# ESP32_with_USB_C.net
KiCad netlist of a schematic drawn in Altium Designer
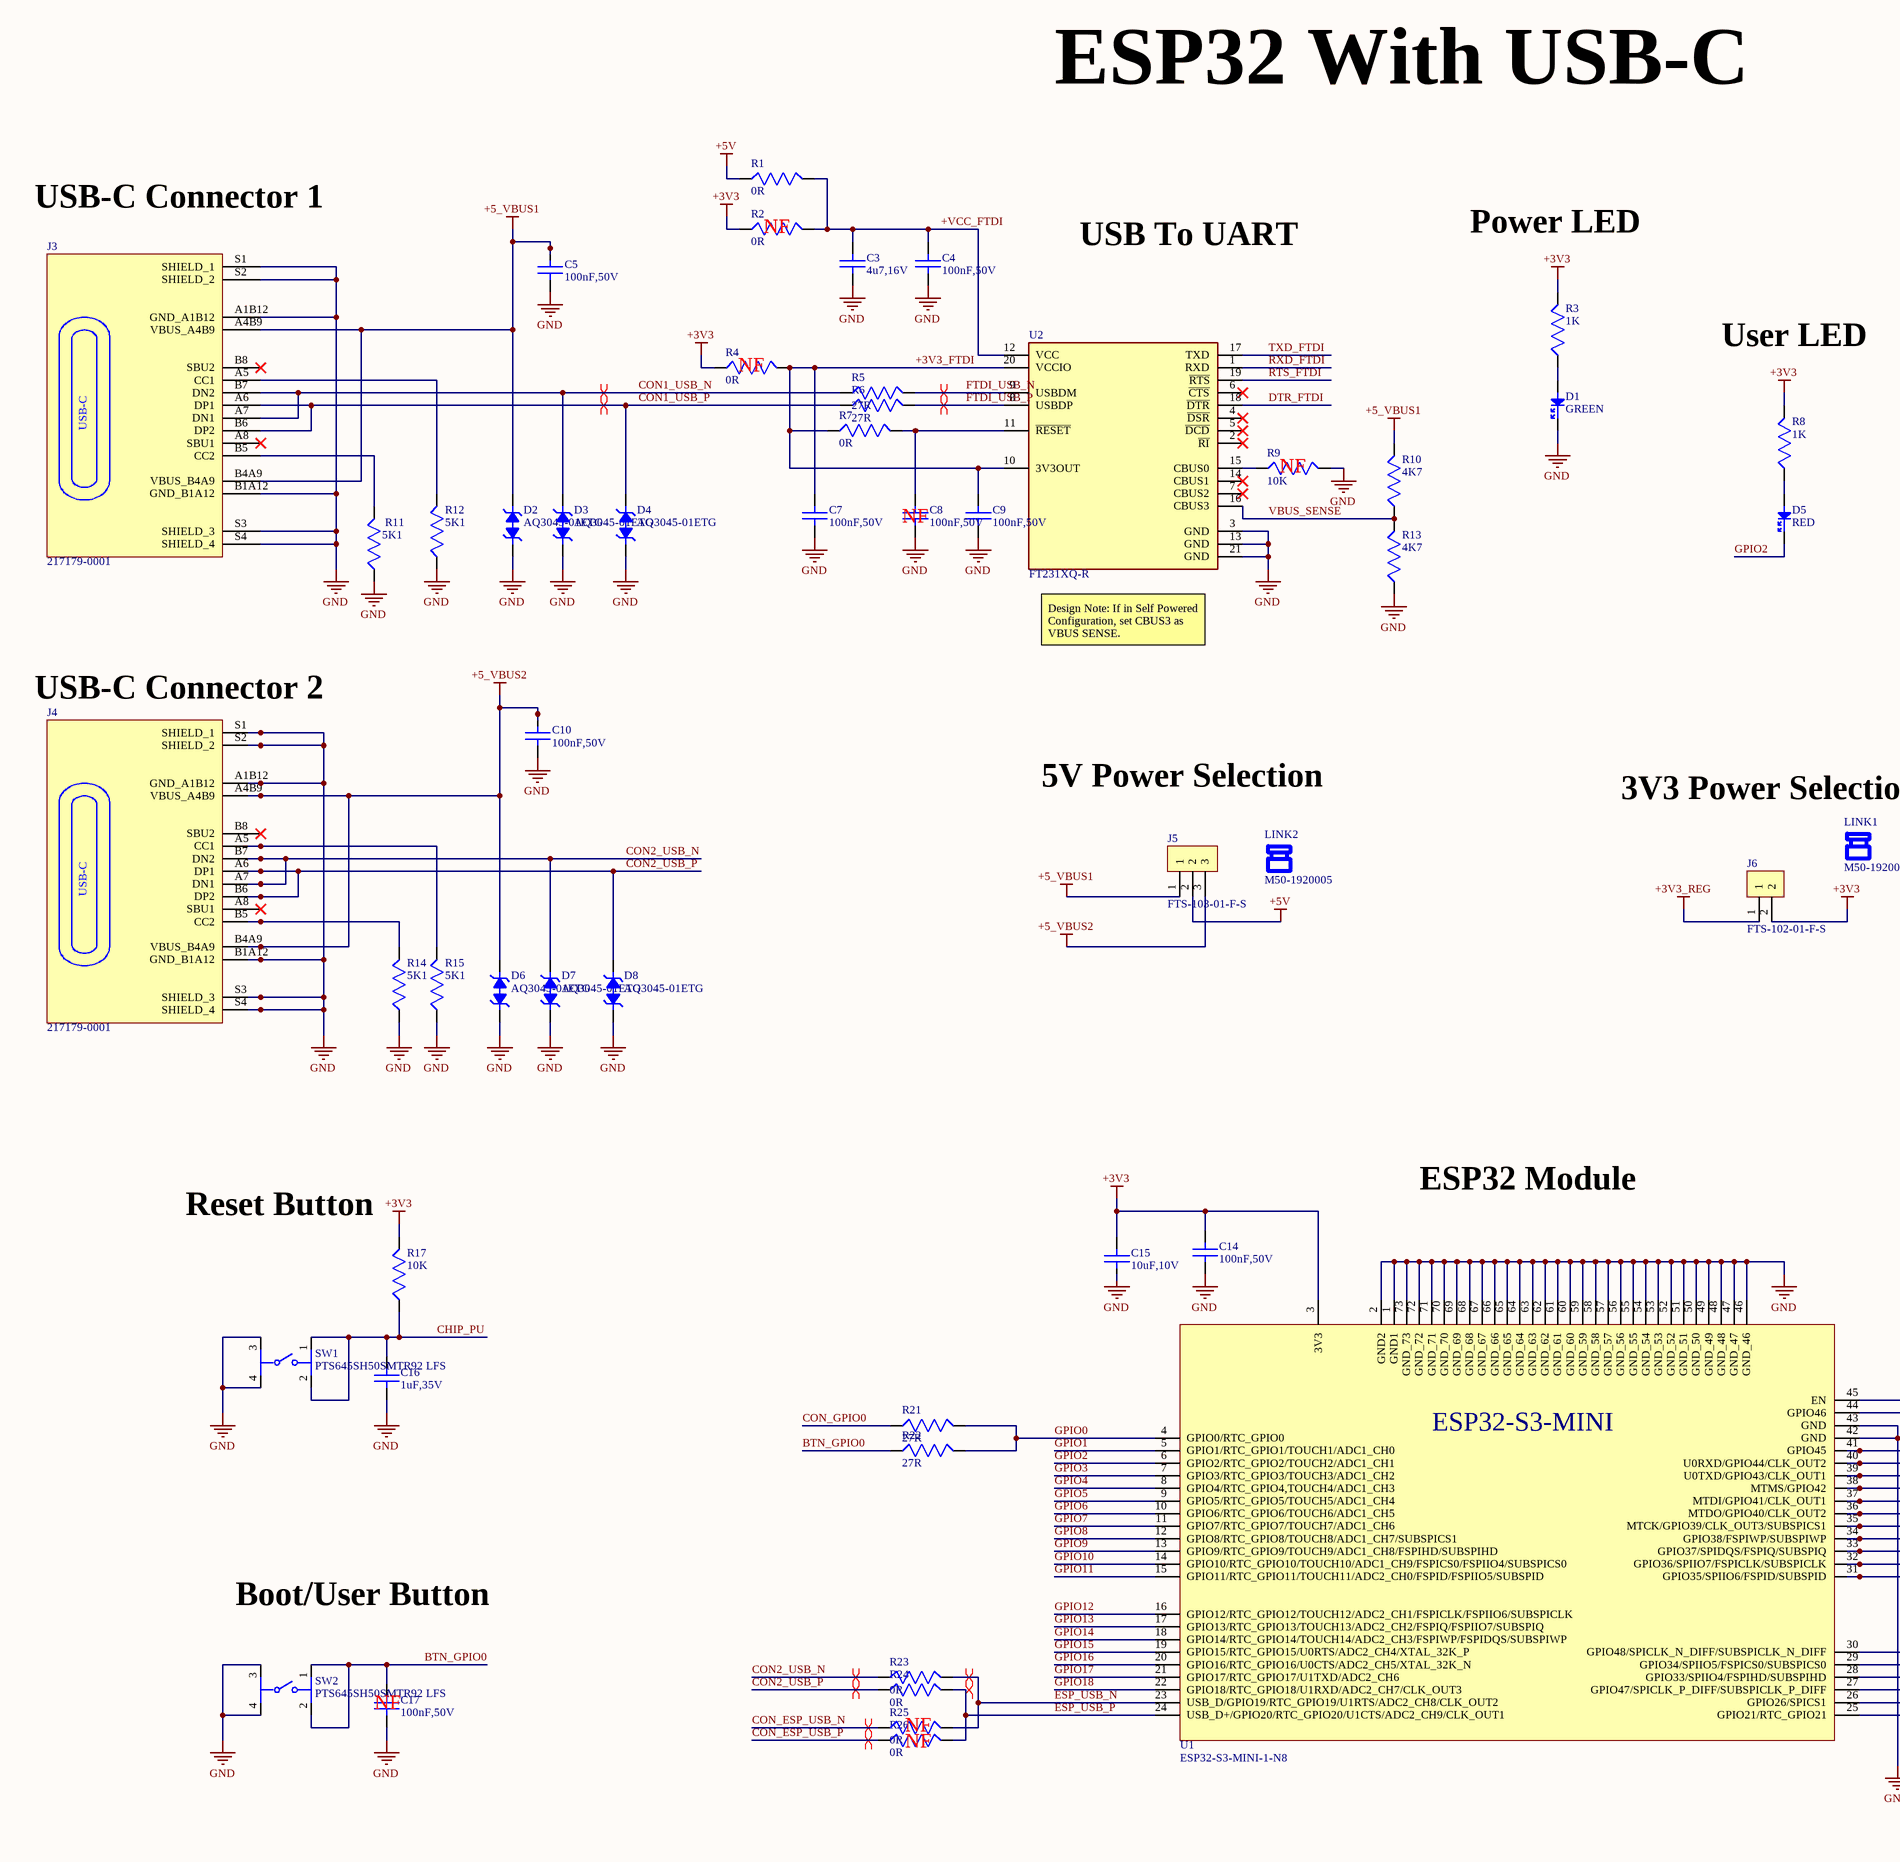
[diagram p0: ESP32 with USB C.SchDoc, left]
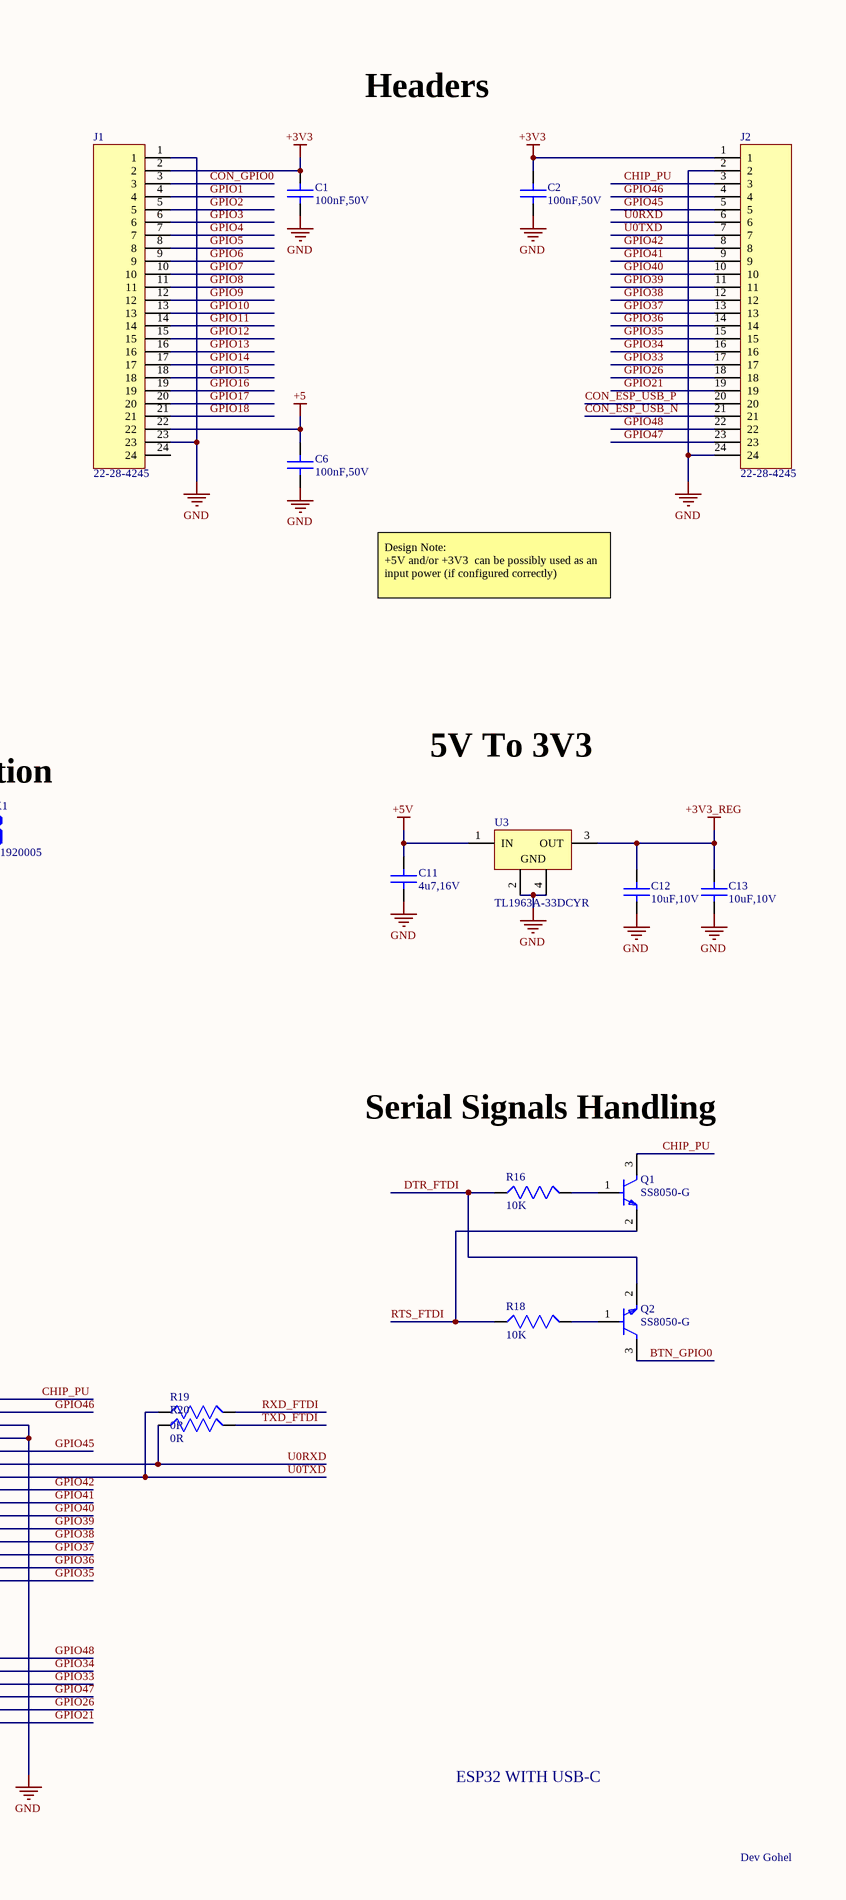
[diagram p1: ESP32 with USB C.SchDoc, right]

(export (version "E")
  (design (tool "Eeschema 10.0.6"))
  (components
    (comp (ref "C1")
      (value "100nF,50V")
      (footprint "CAPC1005X65N")
      (description "CAP CER 0.1UF 50V X7R 0402")
      (fields
        (field (name "MANUFACTURER") "Samsung Electro-Mechanics")
        (field (name "MANUFACTURER PART NUMBER") "CL05B104KB54PNC")
      )
      (libsource (lib "Schlib1") (part "CL05B104KB54PNC"))
    )
    (comp (ref "C2")
      (value "100nF,50V")
      (footprint "CAPC1005X65N")
      (description "CAP CER 0.1UF 50V X7R 0402")
      (fields
        (field (name "MANUFACTURER") "Samsung Electro-Mechanics")
        (field (name "MANUFACTURER PART NUMBER") "CL05B104KB54PNC")
      )
      (libsource (lib "Schlib1") (part "CL05B104KB54PNC"))
    )
    (comp (ref "C3")
      (value "4u7,16V")
      (footprint "CAPC1005X65N")
      (description "CAP CER 4.7UF 16V X5R 0402")
      (fields
        (field (name "MANUFACTURER") "Samsung Electro-Mechanics")
        (field (name "MANUFACTURER PART NUMBER") "CL05A475MO5NUNC")
      )
      (libsource (lib "Schlib1") (part "CL05A475MO5NUNC"))
    )
    (comp (ref "C4")
      (value "100nF,50V")
      (footprint "CAPC1005X65N")
      (description "CAP CER 0.1UF 50V X7R 0402")
      (fields
        (field (name "MANUFACTURER") "Samsung Electro-Mechanics")
        (field (name "MANUFACTURER PART NUMBER") "CL05B104KB54PNC")
      )
      (libsource (lib "Schlib1") (part "CL05B104KB54PNC"))
    )
    (comp (ref "C5")
      (value "100nF,50V")
      (footprint "CAPC1005X65N")
      (description "CAP CER 0.1UF 50V X7R 0402")
      (fields
        (field (name "MANUFACTURER") "Samsung Electro-Mechanics")
        (field (name "MANUFACTURER PART NUMBER") "CL05B104KB54PNC")
      )
      (libsource (lib "Schlib1") (part "CL05B104KB54PNC"))
    )
    (comp (ref "C6")
      (value "100nF,50V")
      (footprint "CAPC1005X65N")
      (description "CAP CER 0.1UF 50V X7R 0402")
      (fields
        (field (name "MANUFACTURER") "Samsung Electro-Mechanics")
        (field (name "MANUFACTURER PART NUMBER") "CL05B104KB54PNC")
      )
      (libsource (lib "Schlib1") (part "CL05B104KB54PNC"))
    )
    (comp (ref "C7")
      (value "100nF,50V")
      (footprint "CAPC1005X65N")
      (description "CAP CER 0.1UF 50V X7R 0402")
      (fields
        (field (name "MANUFACTURER") "Samsung Electro-Mechanics")
        (field (name "MANUFACTURER PART NUMBER") "CL05B104KB54PNC")
      )
      (libsource (lib "Schlib1") (part "CL05B104KB54PNC"))
    )
    (comp (ref "C8")
      (value "100nF,50V")
      (footprint "CAPC1005X65N")
      (description "CAP CER 0.1UF 50V X7R 0402")
      (fields
        (field (name "MANUFACTURER") "Samsung Electro-Mechanics")
        (field (name "MANUFACTURER PART NUMBER") "CL05B104KB54PNC")
      )
      (libsource (lib "Schlib1") (part "CL05B104KB54PNC"))
    )
    (comp (ref "C9")
      (value "100nF,50V")
      (footprint "CAPC1005X65N")
      (description "CAP CER 0.1UF 50V X7R 0402")
      (fields
        (field (name "MANUFACTURER") "Samsung Electro-Mechanics")
        (field (name "MANUFACTURER PART NUMBER") "CL05B104KB54PNC")
      )
      (libsource (lib "Schlib1") (part "CL05B104KB54PNC"))
    )
    (comp (ref "C10")
      (value "100nF,50V")
      (footprint "CAPC1005X65N")
      (description "CAP CER 0.1UF 50V X7R 0402")
      (fields
        (field (name "MANUFACTURER") "Samsung Electro-Mechanics")
        (field (name "MANUFACTURER PART NUMBER") "CL05B104KB54PNC")
      )
      (libsource (lib "Schlib1") (part "CL05B104KB54PNC"))
    )
    (comp (ref "C11")
      (value "4u7,16V")
      (footprint "CAPC1005X65N")
      (description "CAP CER 4.7UF 16V X5R 0402")
      (fields
        (field (name "MANUFACTURER") "Samsung Electro-Mechanics")
        (field (name "MANUFACTURER PART NUMBER") "CL05A475MO5NUNC")
      )
      (libsource (lib "Schlib1") (part "CL05A475MO5NUNC"))
    )
    (comp (ref "C12")
      (value "10uF,10V")
      (footprint "CAPC1005X65N")
      (description "CAP CER 10UF 10V X5R 0402")
      (fields
        (field (name "MANUFACTURER") "Samsung Electro-Mechanics")
        (field (name "MANUFACTURER PART NUMBER") "CL05A106MP8NUB8")
      )
      (libsource (lib "Schlib1") (part "CL05A106MP8NUB8"))
    )
    (comp (ref "C13")
      (value "10uF,10V")
      (footprint "CAPC1005X65N")
      (description "CAP CER 10UF 10V X5R 0402")
      (fields
        (field (name "MANUFACTURER") "Samsung Electro-Mechanics")
        (field (name "MANUFACTURER PART NUMBER") "CL05A106MP8NUB8")
      )
      (libsource (lib "Schlib1") (part "CL05A106MP8NUB8"))
    )
    (comp (ref "C14")
      (value "100nF,50V")
      (footprint "CAPC1005X65N")
      (description "CAP CER 0.1UF 50V X7R 0402")
      (fields
        (field (name "MANUFACTURER") "Samsung Electro-Mechanics")
        (field (name "MANUFACTURER PART NUMBER") "CL05B104KB54PNC")
      )
      (libsource (lib "Schlib1") (part "CL05B104KB54PNC"))
    )
    (comp (ref "C15")
      (value "10uF,10V")
      (footprint "CAPC1005X65N")
      (description "CAP CER 10UF 10V X5R 0402")
      (fields
        (field (name "MANUFACTURER") "Samsung Electro-Mechanics")
        (field (name "MANUFACTURER PART NUMBER") "CL05A106MP8NUB8")
      )
      (libsource (lib "Schlib1") (part "CL05A106MP8NUB8"))
    )
    (comp (ref "C16")
      (value "1uF,35V")
      (footprint "CAPC1005X65N")
      (description "CAP CER 1UF 35V X5R 0402")
      (fields
        (field (name "MANUFACTURER") "Samsung Electro-Mechanics")
        (field (name "MANUFACTURER PART NUMBER") "CL05A105KL5NRNC")
      )
      (libsource (lib "Schlib1") (part "CL05A105KL5NRNC"))
    )
    (comp (ref "C17")
      (value "100nF,50V")
      (footprint "CAPC1005X65N")
      (description "CAP CER 0.1UF 50V X7R 0402")
      (fields
        (field (name "MANUFACTURER") "Samsung Electro-Mechanics")
        (field (name "MANUFACTURER PART NUMBER") "CL05B104KB54PNC")
      )
      (libsource (lib "Schlib1") (part "CL05B104KB54PNC"))
    )
    (comp (ref "D1")
      (value "GREEN")
      (footprint "LED0402G")
      (description "LED YLW-GRN 0402 SMD")
      (fields
        (field (name "MANUFACTURER") "Vishay")
        (field (name "MANUFACTURER PART NUMBER") "VLMG1500-GS08")
      )
      (libsource (lib "Schlib1") (part "VLMG1500-GS08"))
    )
    (comp (ref "D2")
      (value "AQ3045-01ETG")
      (footprint "SOD882")
      (description "TVS DIODE 5.3VWM 12VC SOD882")
      (fields (field (name "MANUFACTURER") "Littelfuse") (field (name "LCSC PART NUMBER") "C3710326"))
      (libsource (lib "Schlib1") (part "AQ3045-01ETG"))
    )
    (comp (ref "D3")
      (value "AQ3045-01ETG")
      (footprint "SOD882")
      (description "TVS DIODE 5.3VWM 12VC SOD882")
      (fields (field (name "MANUFACTURER") "Littelfuse") (field (name "LCSC PART NUMBER") "C3710326"))
      (libsource (lib "Schlib1") (part "AQ3045-01ETG"))
    )
    (comp (ref "D4")
      (value "AQ3045-01ETG")
      (footprint "SOD882")
      (description "TVS DIODE 5.3VWM 12VC SOD882")
      (fields (field (name "MANUFACTURER") "Littelfuse") (field (name "LCSC PART NUMBER") "C3710326"))
      (libsource (lib "Schlib1") (part "AQ3045-01ETG"))
    )
    (comp (ref "D5")
      (value "RED")
      (footprint "LED0402R")
      (description "LED RED 0402 SMD")
      (fields
        (field (name "MANUFACTURER") "Vishay")
        (field (name "MANUFACTURER PART NUMBER") "VLMS1500-GS08")
      )
      (libsource (lib "Schlib1") (part "VLMS1500-GS08"))
    )
    (comp (ref "D6")
      (value "AQ3045-01ETG")
      (footprint "SOD882")
      (description "TVS DIODE 5.3VWM 12VC SOD882")
      (fields (field (name "MANUFACTURER") "Littelfuse") (field (name "LCSC PART NUMBER") "C3710326"))
      (libsource (lib "Schlib1") (part "AQ3045-01ETG"))
    )
    (comp (ref "D7")
      (value "AQ3045-01ETG")
      (footprint "SOD882")
      (description "TVS DIODE 5.3VWM 12VC SOD882")
      (fields (field (name "MANUFACTURER") "Littelfuse") (field (name "LCSC PART NUMBER") "C3710326"))
      (libsource (lib "Schlib1") (part "AQ3045-01ETG"))
    )
    (comp (ref "D8")
      (value "AQ3045-01ETG")
      (footprint "SOD882")
      (description "TVS DIODE 5.3VWM 12VC SOD882")
      (fields (field (name "MANUFACTURER") "Littelfuse") (field (name "LCSC PART NUMBER") "C3710326"))
      (libsource (lib "Schlib1") (part "AQ3045-01ETG"))
    )
    (comp (ref "J1")
      (value "22-28-4245")
      (footprint "HDR_1X24_2.54MM")
      (description "CONN HEADER VERT 24POS 2.54MM")
      (fields (field (name "MANUFACTURER") "Molex") (field (name "LCSC PART NUMBER") "C7145888"))
      (libsource (lib "") (part "22-28-4245_1"))
    )
    (comp (ref "J2")
      (value "22-28-4245")
      (footprint "HDR_1X24_2.54MM")
      (description "CONN HEADER VERT 24POS 2.54MM")
      (fields (field (name "MANUFACTURER") "Molex") (field (name "LCSC PART NUMBER") "C7145888"))
      (libsource (lib "Schlib1") (part "22-28-4245"))
    )
    (comp (ref "J3")
      (value "217179-0001")
      (footprint "FP-2171790001-MFG")
      (description "CONN RCP USB2.0 TYP C 24P SMD RA")
      (fields (field (name "MANUFACTURER") "Molex") (field (name "LCSC PART NUMBER") "C3197684"))
      (libsource (lib "Schlib1") (part "217179-0001"))
    )
    (comp (ref "J4")
      (value "217179-0001")
      (footprint "FP-2171790001-MFG")
      (description "CONN RCP USB2.0 TYP C 24P SMD RA")
      (fields (field (name "MANUFACTURER") "Molex") (field (name "LCSC PART NUMBER") "C3197684"))
      (libsource (lib "Schlib1") (part "217179-0001"))
    )
    (comp (ref "J5")
      (value "FTS-103-01-F-S")
      (footprint "HDR_1X3_1.27MM")
      (description "CONN HEADER VERT 3POS 1.27MM")
      (fields (field (name "MANUFACTURER") "Samtec") (field (name "LCSC PART NUMBER") "C3333578"))
      (libsource (lib "Schlib1") (part "FTS-103-01-F-S"))
    )
    (comp (ref "J6")
      (value "FTS-102-01-F-S")
      (footprint "HDR_1X2_1.27MM")
      (description "CONN HEADER VERT 2POS 1.27MM")
      (fields (field (name "MANUFACTURER") "Samtec") (field (name "LCSC PART NUMBER") "C6045317"))
      (libsource (lib "Schlib1") (part "FTS-102-01-F-S"))
    )
    (comp (ref "LINK1")
      (value "M50-1920005")
      (description "CONN SHUNT 1.27MM RED")
      (fields (field (name "MANUFACTURER") "Harwin") (field (name "LCSC PART NUMBER") "C6985646"))
      (libsource (lib "Schlib1") (part "M50-1920005"))
    )
    (comp (ref "LINK2")
      (value "M50-1920005")
      (description "CONN SHUNT 1.27MM RED")
      (fields (field (name "MANUFACTURER") "Harwin") (field (name "LCSC PART NUMBER") "C6985646"))
      (libsource (lib "Schlib1") (part "M50-1920005"))
    )
    (comp (ref "Q1")
      (value "SS8050-G")
      (footprint "FP-SS8050-G-IPC_B")
      (description "TRANS NPN 25V 1.5A SOT-23-3")
      (fields (field (name "MANUFACTURER") "Comchip") (field (name "LCSC PART NUMBER") "C164886"))
      (libsource (lib "Schlib1") (part "SS8050-G"))
    )
    (comp (ref "Q2")
      (value "SS8050-G")
      (footprint "FP-SS8050-G-IPC_B")
      (description "TRANS NPN 25V 1.5A SOT-23-3")
      (fields (field (name "MANUFACTURER") "Comchip") (field (name "LCSC PART NUMBER") "C164886"))
      (libsource (lib "Schlib1") (part "SS8050-G"))
    )
    (comp (ref "R1")
      (value "0R")
      (footprint "RESC1005X37N")
      (description "RES 0 OHM JUMPER 1/16W 0402")
      (fields
        (field (name "MANUFACTURER") "Yageo Group")
        (field (name "MANUFACTURER PART NUMBER") "RC0402JR-070RL")
      )
      (libsource (lib "Schlib1") (part "RC0402JR-070RL"))
    )
    (comp (ref "R2")
      (value "0R")
      (footprint "RESC1005X37N")
      (description "RES 0 OHM JUMPER 1/16W 0402")
      (fields
        (field (name "MANUFACTURER") "Yageo Group")
        (field (name "MANUFACTURER PART NUMBER") "RC0402JR-070RL")
      )
      (libsource (lib "Schlib1") (part "RC0402JR-070RL"))
    )
    (comp (ref "R3")
      (value "1K")
      (footprint "RESC1005X37N")
      (description "RES 1K OHM 1% 1/16W 0402")
      (fields
        (field (name "MANUFACTURER") "Yageo Group")
        (field (name "MANUFACTURER PART NUMBER") "RC0402FR-071KL")
      )
      (libsource (lib "Schlib1") (part "RC0402FR-071KL"))
    )
    (comp (ref "R4")
      (value "0R")
      (footprint "RESC1005X37N")
      (description "RES 0 OHM JUMPER 1/16W 0402")
      (fields
        (field (name "MANUFACTURER") "Yageo Group")
        (field (name "MANUFACTURER PART NUMBER") "RC0402JR-070RL")
      )
      (libsource (lib "Schlib1") (part "RC0402JR-070RL"))
    )
    (comp (ref "R5")
      (value "27R")
      (footprint "RESC1005X37N")
      (description "RES 27 OHM 1% 1/16W 0402")
      (fields
        (field (name "MANUFACTURER") "Yageo Group")
        (field (name "MANUFACTURER PART NUMBER") "RC0402FR-0727RL")
      )
      (libsource (lib "Schlib1") (part "RC0402FR-0727RL"))
    )
    (comp (ref "R6")
      (value "27R")
      (footprint "RESC1005X37N")
      (description "RES 27 OHM 1% 1/16W 0402")
      (fields
        (field (name "MANUFACTURER") "Yageo Group")
        (field (name "MANUFACTURER PART NUMBER") "RC0402FR-0727RL")
      )
      (libsource (lib "Schlib1") (part "RC0402FR-0727RL"))
    )
    (comp (ref "R7")
      (value "0R")
      (footprint "RESC1005X37N")
      (description "RES 0 OHM JUMPER 1/16W 0402")
      (fields
        (field (name "MANUFACTURER") "Yageo Group")
        (field (name "MANUFACTURER PART NUMBER") "RC0402JR-070RL")
      )
      (libsource (lib "Schlib1") (part "RC0402JR-070RL"))
    )
    (comp (ref "R8")
      (value "1K")
      (footprint "RESC1005X37N")
      (description "RES 1K OHM 1% 1/16W 0402")
      (fields
        (field (name "MANUFACTURER") "Yageo Group")
        (field (name "MANUFACTURER PART NUMBER") "RC0402FR-071KL")
      )
      (libsource (lib "Schlib1") (part "RC0402FR-071KL"))
    )
    (comp (ref "R9")
      (value "10K")
      (footprint "RESC1005X37N")
      (description "RES SMD 10K OHM 1% 1/16W 0402")
      (fields
        (field (name "MANUFACTURER") "Yageo Group")
        (field (name "MANUFACTURER PART NUMBER") "AC0402FR-0710KL")
      )
      (libsource (lib "Schlib1") (part "AC0402FR-0710KL"))
    )
    (comp (ref "R10")
      (value "4K7")
      (footprint "RESC1005X37N")
      (description "RES 4.7K OHM 1% 1/16W 0402")
      (fields
        (field (name "MANUFACTURER") "Yageo Group")
        (field (name "MANUFACTURER PART NUMBER") "RC0402FR-074K7L")
      )
      (libsource (lib "Schlib1") (part "RC0402FR-074K7L"))
    )
    (comp (ref "R11")
      (value "5K1")
      (footprint "RESC1005X37N")
      (description "RES SMD 5.1K OHM 1% 1/16W 0402")
      (fields
        (field (name "MANUFACTURER") "Yageo Group")
        (field (name "MANUFACTURER PART NUMBER") "AC0402FR-075K1L")
      )
      (libsource (lib "Schlib1") (part "AC0402FR-075K1L"))
    )
    (comp (ref "R12")
      (value "5K1")
      (footprint "RESC1005X37N")
      (description "RES SMD 5.1K OHM 1% 1/16W 0402")
      (fields
        (field (name "MANUFACTURER") "Yageo Group")
        (field (name "MANUFACTURER PART NUMBER") "AC0402FR-075K1L")
      )
      (libsource (lib "Schlib1") (part "AC0402FR-075K1L"))
    )
    (comp (ref "R13")
      (value "4K7")
      (footprint "RESC1005X37N")
      (description "RES 4.7K OHM 1% 1/16W 0402")
      (fields
        (field (name "MANUFACTURER") "Yageo Group")
        (field (name "MANUFACTURER PART NUMBER") "RC0402FR-074K7L")
      )
      (libsource (lib "Schlib1") (part "RC0402FR-074K7L"))
    )
    (comp (ref "R14")
      (value "5K1")
      (footprint "RESC1005X37N")
      (description "RES SMD 5.1K OHM 1% 1/16W 0402")
      (fields
        (field (name "MANUFACTURER") "Yageo Group")
        (field (name "MANUFACTURER PART NUMBER") "AC0402FR-075K1L")
      )
      (libsource (lib "Schlib1") (part "AC0402FR-075K1L"))
    )
    (comp (ref "R15")
      (value "5K1")
      (footprint "RESC1005X37N")
      (description "RES SMD 5.1K OHM 1% 1/16W 0402")
      (fields
        (field (name "MANUFACTURER") "Yageo Group")
        (field (name "MANUFACTURER PART NUMBER") "AC0402FR-075K1L")
      )
      (libsource (lib "Schlib1") (part "AC0402FR-075K1L"))
    )
    (comp (ref "R16")
      (value "10K")
      (footprint "RESC1005X37N")
      (description "RES SMD 10K OHM 1% 1/16W 0402")
      (fields
        (field (name "MANUFACTURER") "Yageo Group")
        (field (name "MANUFACTURER PART NUMBER") "AC0402FR-0710KL")
      )
      (libsource (lib "Schlib1") (part "AC0402FR-0710KL"))
    )
    (comp (ref "R17")
      (value "10K")
      (footprint "RESC1005X37N")
      (description "RES SMD 10K OHM 1% 1/16W 0402")
      (fields
        (field (name "MANUFACTURER") "Yageo Group")
        (field (name "MANUFACTURER PART NUMBER") "AC0402FR-0710KL")
      )
      (libsource (lib "Schlib1") (part "AC0402FR-0710KL"))
    )
    (comp (ref "R18")
      (value "10K")
      (footprint "RESC1005X37N")
      (description "RES SMD 10K OHM 1% 1/16W 0402")
      (fields
        (field (name "MANUFACTURER") "Yageo Group")
        (field (name "MANUFACTURER PART NUMBER") "AC0402FR-0710KL")
      )
      (libsource (lib "Schlib1") (part "AC0402FR-0710KL"))
    )
    (comp (ref "R19")
      (value "0R")
      (footprint "RESC1005X37N")
      (description "RES 0 OHM JUMPER 1/16W 0402")
      (fields
        (field (name "MANUFACTURER") "Yageo Group")
        (field (name "MANUFACTURER PART NUMBER") "RC0402JR-070RL")
      )
      (libsource (lib "Schlib1") (part "RC0402JR-070RL"))
    )
    (comp (ref "R20")
      (value "0R")
      (footprint "RESC1005X37N")
      (description "RES 0 OHM JUMPER 1/16W 0402")
      (fields
        (field (name "MANUFACTURER") "Yageo Group")
        (field (name "MANUFACTURER PART NUMBER") "RC0402JR-070RL")
      )
      (libsource (lib "Schlib1") (part "RC0402JR-070RL"))
    )
    (comp (ref "R21")
      (value "27R")
      (footprint "RESC1005X37N")
      (description "RES 27 OHM 1% 1/16W 0402")
      (fields
        (field (name "MANUFACTURER") "Yageo Group")
        (field (name "MANUFACTURER PART NUMBER") "RC0402FR-0727RL")
      )
      (libsource (lib "Schlib1") (part "RC0402FR-0727RL"))
    )
    (comp (ref "R22")
      (value "27R")
      (footprint "RESC1005X37N")
      (description "RES 27 OHM 1% 1/16W 0402")
      (fields
        (field (name "MANUFACTURER") "Yageo Group")
        (field (name "MANUFACTURER PART NUMBER") "RC0402FR-0727RL")
      )
      (libsource (lib "Schlib1") (part "RC0402FR-0727RL"))
    )
    (comp (ref "R23")
      (value "0R")
      (footprint "RESC1005X37N")
      (description "RES 0 OHM JUMPER 1/16W 0402")
      (fields
        (field (name "MANUFACTURER") "Yageo Group")
        (field (name "MANUFACTURER PART NUMBER") "RC0402JR-070RL")
      )
      (libsource (lib "Schlib1") (part "RC0402JR-070RL"))
    )
    (comp (ref "R24")
      (value "0R")
      (footprint "RESC1005X37N")
      (description "RES 0 OHM JUMPER 1/16W 0402")
      (fields
        (field (name "MANUFACTURER") "Yageo Group")
        (field (name "MANUFACTURER PART NUMBER") "RC0402JR-070RL")
      )
      (libsource (lib "Schlib1") (part "RC0402JR-070RL"))
    )
    (comp (ref "R25")
      (value "0R")
      (footprint "RESC1005X37N")
      (description "RES 0 OHM JUMPER 1/16W 0402")
      (fields
        (field (name "MANUFACTURER") "Yageo Group")
        (field (name "MANUFACTURER PART NUMBER") "RC0402JR-070RL")
      )
      (libsource (lib "Schlib1") (part "RC0402JR-070RL"))
    )
    (comp (ref "R26")
      (value "0R")
      (footprint "RESC1005X37N")
      (description "RES 0 OHM JUMPER 1/16W 0402")
      (fields
        (field (name "MANUFACTURER") "Yageo Group")
        (field (name "MANUFACTURER PART NUMBER") "RC0402JR-070RL")
      )
      (libsource (lib "Schlib1") (part "RC0402JR-070RL"))
    )
    (comp (ref "SW1")
      (value "PTS645SH50SMTR92 LFS")
      (footprint "FP-PTS645SH50SMTR92LFS-MFG")
      (description "SWITCH TACTILE SPST-NO 0.05A 12V")
      (fields
        (field (name "MANUFACTURER") "C&K Components")
        (field (name "MANUFACTURER PART NUMBER") "PTS645SH50SMTR92LFS")
      )
      (libsource (lib "Schlib1") (part "PTS645SH50SMTR92LFS"))
    )
    (comp (ref "SW2")
      (value "PTS645SH50SMTR92 LFS")
      (footprint "FP-PTS645SH50SMTR92LFS-MFG")
      (description "SWITCH TACTILE SPST-NO 0.05A 12V")
      (fields
        (field (name "MANUFACTURER") "C&K Components")
        (field (name "MANUFACTURER PART NUMBER") "PTS645SH50SMTR92LFS")
      )
      (libsource (lib "Schlib1") (part "PTS645SH50SMTR92LFS"))
    )
    (comp (ref "U1")
      (value "ESP32-S3-MINI-1-N8")
      (footprint "XCVR_ESP32-S3-MINI-1-N8")
      (description "SMD module, ESP32-S3FN8, 8 MB SPI flash, PCB antenna")
      (fields (field (name "MANUFACTURER") "Espressif Systems") (field (name "LCSC PART NUMBER") "C2913206"))
      (libsource (lib "Schlib1") (part "ESP32-S3-MINI-1-N8_1"))
    )
    (comp (ref "U2")
      (value "FT231XQ-R")
      (footprint "FP-QFN-20-IPC_B")
      (description "IC USB SERIAL FULL UART 20QFN")
      (fields (field (name "MANUFACTURER") "FTDI") (field (name "LCSC PART NUMBER") "C132159"))
      (libsource (lib "Schlib1") (part "FT231XQ-R"))
    )
    (comp (ref "U3")
      (value "TL1963A-33DCYR")
      (footprint "DCY0004A_N")
      (description "IC REG LIN 3.3V 1.5A SOT-223-4")
      (fields (field (name "MANUFACTURER") "Texas Instruments") (field (name "LCSC PART NUMBER") "C181262"))
      (libsource (lib "Schlib1") (part "TL1963A-33DCYR"))
    )
  )
  (nets
    (net (code "1") (name "+3V3") (class "Default")
      (node (ref "C1") (pin "2") (pinfunction "2_2") (pintype "passive"))
      (node (ref "C14") (pin "2") (pinfunction "2_2") (pintype "passive"))
      (node (ref "C15") (pin "2") (pinfunction "2_2") (pintype "passive"))
      (node (ref "C2") (pin "2") (pinfunction "2_2") (pintype "passive"))
      (node (ref "J1") (pin "2") (pinfunction "2_2") (pintype "passive"))
      (node (ref "J2") (pin "1") (pinfunction "1_1") (pintype "passive"))
      (node (ref "J6") (pin "2") (pinfunction "2_2") (pintype "passive"))
      (node (ref "R17") (pin "2") (pinfunction "2_2") (pintype "passive"))
      (node (ref "R2") (pin "1") (pinfunction "1_1") (pintype "passive"))
      (node (ref "R3") (pin "2") (pinfunction "2_2") (pintype "passive"))
      (node (ref "R4") (pin "1") (pinfunction "1_1") (pintype "passive"))
      (node (ref "R8") (pin "2") (pinfunction "2_2") (pintype "passive"))
      (node (ref "U1") (pin "3") (pinfunction "3V3_3") (pintype "passive"))
    )
    (net (code "2") (name "+3V3_REG") (class "Default")
      (node (ref "C12") (pin "2") (pinfunction "2_2") (pintype "passive"))
      (node (ref "C13") (pin "2") (pinfunction "2_2") (pintype "passive"))
      (node (ref "J6") (pin "1") (pinfunction "1_1") (pintype "passive"))
      (node (ref "U3") (pin "3") (pinfunction "OUT_3") (pintype "power_in"))
    )
    (net (code "3") (name "+5") (class "Default")
      (node (ref "C6") (pin "2") (pinfunction "2_2") (pintype "passive"))
      (node (ref "J1") (pin "22") (pinfunction "22_22") (pintype "passive"))
    )
    (net (code "4") (name "+5V") (class "Default")
      (node (ref "C11") (pin "2") (pinfunction "2_2") (pintype "passive"))
      (node (ref "J5") (pin "2") (pinfunction "2_2") (pintype "passive"))
      (node (ref "R1") (pin "1") (pinfunction "1_1") (pintype "passive"))
      (node (ref "U3") (pin "1") (pinfunction "IN_1") (pintype "power_in"))
    )
    (net (code "5") (name "+5_VBUS1") (class "Default")
      (node (ref "C5") (pin "2") (pinfunction "2_2") (pintype "passive"))
      (node (ref "D2") (pin "2") (pinfunction "2_2") (pintype "passive"))
      (node (ref "J3") (pin "A4B9") (pinfunction "VBUS_A4B9_A4B9") (pintype "passive"))
      (node (ref "J3") (pin "B4A9") (pinfunction "VBUS_B4A9_B4A9") (pintype "passive"))
      (node (ref "J5") (pin "1") (pinfunction "1_1") (pintype "passive"))
      (node (ref "R10") (pin "2") (pinfunction "2_2") (pintype "passive"))
    )
    (net (code "6") (name "+5_VBUS2") (class "Default")
      (node (ref "C10") (pin "2") (pinfunction "2_2") (pintype "passive"))
      (node (ref "D6") (pin "2") (pinfunction "2_2") (pintype "passive"))
      (node (ref "J4") (pin "A4B9") (pinfunction "VBUS_A4B9_A4B9") (pintype "passive"))
      (node (ref "J4") (pin "B4A9") (pinfunction "VBUS_B4A9_B4A9") (pintype "passive"))
      (node (ref "J5") (pin "3") (pinfunction "3_3") (pintype "passive"))
    )
    (net (code "7") (name "/+3V3_FTDI") (class "Default")
      (node (ref "C7") (pin "2") (pinfunction "2_2") (pintype "passive"))
      (node (ref "C9") (pin "2") (pinfunction "2_2") (pintype "passive"))
      (node (ref "R4") (pin "2") (pinfunction "2_2") (pintype "passive"))
      (node (ref "R7") (pin "1") (pinfunction "1_1") (pintype "passive"))
      (node (ref "U2") (pin "10") (pinfunction "3V3OUT_10") (pintype "passive"))
      (node (ref "U2") (pin "20") (pinfunction "VCCIO_20") (pintype "passive"))
    )
    (net (code "8") (name "/+VCC_FTDI") (class "Default")
      (node (ref "C3") (pin "2") (pinfunction "2_2") (pintype "passive"))
      (node (ref "C4") (pin "2") (pinfunction "2_2") (pintype "passive"))
      (node (ref "R1") (pin "2") (pinfunction "2_2") (pintype "passive"))
      (node (ref "R2") (pin "2") (pinfunction "2_2") (pintype "passive"))
      (node (ref "U2") (pin "12") (pinfunction "VCC_12") (pintype "passive"))
    )
    (net (code "9") (name "/BTN_GPIO0") (class "Default")
      (node (ref "C17") (pin "2") (pinfunction "2_2") (pintype "passive"))
      (node (ref "Q2") (pin "3") (pinfunction "C_3") (pintype "passive"))
      (node (ref "R22") (pin "1") (pinfunction "1_1") (pintype "passive"))
      (node (ref "SW2") (pin "1") (pinfunction "1_1") (pintype "passive"))
      (node (ref "SW2") (pin "2") (pinfunction "2_2") (pintype "passive"))
    )
    (net (code "10") (name "/CHIP_PU") (class "Default")
      (node (ref "C16") (pin "2") (pinfunction "2_2") (pintype "passive"))
      (node (ref "J2") (pin "3") (pinfunction "3_3") (pintype "passive"))
      (node (ref "Q1") (pin "3") (pinfunction "C_3") (pintype "passive"))
      (node (ref "R17") (pin "1") (pinfunction "1_1") (pintype "passive"))
      (node (ref "SW1") (pin "1") (pinfunction "1_1") (pintype "passive"))
      (node (ref "SW1") (pin "2") (pinfunction "2_2") (pintype "passive"))
      (node (ref "U1") (pin "45") (pinfunction "EN_45") (pintype "passive"))
    )
    (net (code "11") (name "/CON1_USB_N") (class "Default")
      (node (ref "D3") (pin "2") (pinfunction "2_2") (pintype "passive"))
      (node (ref "J3") (pin "A7") (pinfunction "DN1_A7") (pintype "passive"))
      (node (ref "J3") (pin "B7") (pinfunction "DN2_B7") (pintype "passive"))
      (node (ref "R5") (pin "1") (pinfunction "1_1") (pintype "passive"))
    )
    (net (code "12") (name "/CON1_USB_P") (class "Default")
      (node (ref "D4") (pin "2") (pinfunction "2_2") (pintype "passive"))
      (node (ref "J3") (pin "A6") (pinfunction "DP1_A6") (pintype "passive"))
      (node (ref "J3") (pin "B6") (pinfunction "DP2_B6") (pintype "passive"))
      (node (ref "R6") (pin "1") (pinfunction "1_1") (pintype "passive"))
    )
    (net (code "13") (name "/CON2_USB_N") (class "Default")
      (node (ref "D7") (pin "2") (pinfunction "2_2") (pintype "passive"))
      (node (ref "J4") (pin "A7") (pinfunction "DN1_A7") (pintype "passive"))
      (node (ref "J4") (pin "B7") (pinfunction "DN2_B7") (pintype "passive"))
      (node (ref "R23") (pin "1") (pinfunction "1_1") (pintype "passive"))
    )
    (net (code "14") (name "/CON2_USB_P") (class "Default")
      (node (ref "D8") (pin "2") (pinfunction "2_2") (pintype "passive"))
      (node (ref "J4") (pin "A6") (pinfunction "DP1_A6") (pintype "passive"))
      (node (ref "J4") (pin "B6") (pinfunction "DP2_B6") (pintype "passive"))
      (node (ref "R24") (pin "1") (pinfunction "1_1") (pintype "passive"))
    )
    (net (code "15") (name "/CON_ESP_USB_N") (class "Default")
      (node (ref "J2") (pin "21") (pinfunction "21_21") (pintype "passive"))
      (node (ref "R25") (pin "1") (pinfunction "1_1") (pintype "passive"))
    )
    (net (code "16") (name "/CON_ESP_USB_P") (class "Default")
      (node (ref "J2") (pin "20") (pinfunction "20_20") (pintype "passive"))
      (node (ref "R26") (pin "1") (pinfunction "1_1") (pintype "passive"))
    )
    (net (code "17") (name "/CON_GPIO0") (class "Default")
      (node (ref "J1") (pin "3") (pinfunction "3_3") (pintype "passive"))
      (node (ref "R21") (pin "1") (pinfunction "1_1") (pintype "passive"))
    )
    (net (code "18") (name "/DTR_FTDI") (class "Default")
      (node (ref "Q2") (pin "2") (pinfunction "E_2") (pintype "passive"))
      (node (ref "R16") (pin "1") (pinfunction "1_1") (pintype "passive"))
      (node (ref "U2") (pin "18") (pinfunction "~{DTR}_18") (pintype "passive"))
    )
    (net (code "19") (name "/ESP_USB_N") (class "Default")
      (node (ref "R23") (pin "2") (pinfunction "2_2") (pintype "passive"))
      (node (ref "R25") (pin "2") (pinfunction "2_2") (pintype "passive"))
      (node (ref "U1") (pin "23") (pinfunction "USB_D/GPIO19/RTC_GPIO19/U1RTS/ADC2_CH8/CLK_OUT2_23") (pintype "passive"))
    )
    (net (code "20") (name "/ESP_USB_P") (class "Default")
      (node (ref "R24") (pin "2") (pinfunction "2_2") (pintype "passive"))
      (node (ref "R26") (pin "2") (pinfunction "2_2") (pintype "passive"))
      (node (ref "U1") (pin "24") (pinfunction "USB_D+/GPIO20/RTC_GPIO20/U1CTS/ADC2_CH9/CLK_OUT1_24") (pintype "passive"))
    )
    (net (code "21") (name "/FTDI_USB_N") (class "Default")
      (node (ref "R5") (pin "2") (pinfunction "2_2") (pintype "passive"))
      (node (ref "U2") (pin "9") (pinfunction "USBDM_9") (pintype "passive"))
    )
    (net (code "22") (name "/FTDI_USB_P") (class "Default")
      (node (ref "R6") (pin "2") (pinfunction "2_2") (pintype "passive"))
      (node (ref "U2") (pin "8") (pinfunction "USBDP_8") (pintype "passive"))
    )
    (net (code "23") (name "/GPIO0") (class "Default")
      (node (ref "R21") (pin "2") (pinfunction "2_2") (pintype "passive"))
      (node (ref "R22") (pin "2") (pinfunction "2_2") (pintype "passive"))
      (node (ref "U1") (pin "4") (pinfunction "GPIO0/RTC_GPIO0_4") (pintype "passive"))
    )
    (net (code "24") (name "/GPIO1") (class "Default")
      (node (ref "J1") (pin "4") (pinfunction "4_4") (pintype "passive"))
      (node (ref "U1") (pin "5") (pinfunction "GPIO1/RTC_GPIO1/TOUCH1/ADC1_CH0_5") (pintype "passive"))
    )
    (net (code "25") (name "/GPIO2") (class "Default")
      (node (ref "D5") (pin "1") (pinfunction "1_1") (pintype "passive"))
      (node (ref "J1") (pin "5") (pinfunction "5_5") (pintype "passive"))
      (node (ref "U1") (pin "6") (pinfunction "GPIO2/RTC_GPIO2/TOUCH2/ADC1_CH1_6") (pintype "passive"))
    )
    (net (code "26") (name "/GPIO3") (class "Default")
      (node (ref "J1") (pin "6") (pinfunction "6_6") (pintype "passive"))
      (node (ref "U1") (pin "7") (pinfunction "GPIO3/RTC_GPIO3/TOUCH3/ADC1_CH2_7") (pintype "passive"))
    )
    (net (code "27") (name "/GPIO4") (class "Default")
      (node (ref "J1") (pin "7") (pinfunction "7_7") (pintype "passive"))
      (node (ref "U1") (pin "8") (pinfunction "GPIO4/RTC_GPIO4,TOUCH4/ADC1_CH3_8") (pintype "passive"))
    )
    (net (code "28") (name "/GPIO5") (class "Default")
      (node (ref "J1") (pin "8") (pinfunction "8_8") (pintype "passive"))
      (node (ref "U1") (pin "9") (pinfunction "GPIO5/RTC_GPIO5/TOUCH5/ADC1_CH4_9") (pintype "passive"))
    )
    (net (code "29") (name "/GPIO6") (class "Default")
      (node (ref "J1") (pin "9") (pinfunction "9_9") (pintype "passive"))
      (node (ref "U1") (pin "10") (pinfunction "GPIO6/RTC_GPIO6/TOUCH6/ADC1_CH5_10") (pintype "passive"))
    )
    (net (code "30") (name "/GPIO7") (class "Default")
      (node (ref "J1") (pin "10") (pinfunction "10_10") (pintype "passive"))
      (node (ref "U1") (pin "11") (pinfunction "GPIO7/RTC_GPIO7/TOUCH7/ADC1_CH6_11") (pintype "passive"))
    )
    (net (code "31") (name "/GPIO8") (class "Default")
      (node (ref "J1") (pin "11") (pinfunction "11_11") (pintype "passive"))
      (node (ref "U1") (pin "12") (pinfunction "GPIO8/RTC_GPIO8/TOUCH8/ADC1_CH7/SUBSPICS1_12") (pintype "passive"))
    )
    (net (code "32") (name "/GPIO9") (class "Default")
      (node (ref "J1") (pin "12") (pinfunction "12_12") (pintype "passive"))
      (node (ref "U1") (pin "13") (pinfunction "GPIO9/RTC_GPIO9/TOUCH9/ADC1_CH8/FSPIHD/SUBSPIHD_13") (pintype "passive"))
    )
    (net (code "33") (name "/GPIO10") (class "Default")
      (node (ref "J1") (pin "13") (pinfunction "13_13") (pintype "passive"))
      (node (ref "U1") (pin "14") (pinfunction "GPIO10/RTC_GPIO10/TOUCH10/ADC1_CH9/FSPICS0/FSPIIO4/SUBSPICS0_14") (pintype "passive"))
    )
    (net (code "34") (name "/GPIO11") (class "Default")
      (node (ref "J1") (pin "14") (pinfunction "14_14") (pintype "passive"))
      (node (ref "U1") (pin "15") (pinfunction "GPIO11/RTC_GPIO11/TOUCH11/ADC2_CH0/FSPID/FSPIIO5/SUBSPID_15") (pintype "passive"))
    )
    (net (code "35") (name "/GPIO12") (class "Default")
      (node (ref "J1") (pin "15") (pinfunction "15_15") (pintype "passive"))
      (node (ref "U1") (pin "16") (pinfunction "GPIO12/RTC_GPIO12/TOUCH12/ADC2_CH1/FSPICLK/FSPIIO6/SUBSPICLK_16") (pintype "passive"))
    )
    (net (code "36") (name "/GPIO13") (class "Default")
      (node (ref "J1") (pin "16") (pinfunction "16_16") (pintype "passive"))
      (node (ref "U1") (pin "17") (pinfunction "GPIO13/RTC_GPIO13/TOUCH13/ADC2_CH2/FSPIQ/FSPIIO7/SUBSPIQ_17") (pintype "passive"))
    )
    (net (code "37") (name "/GPIO14") (class "Default")
      (node (ref "J1") (pin "17") (pinfunction "17_17") (pintype "passive"))
      (node (ref "U1") (pin "18") (pinfunction "GPIO14/RTC_GPIO14/TOUCH14/ADC2_CH3/FSPIWP/FSPIDQS/SUBSPIWP_18") (pintype "passive"))
    )
    (net (code "38") (name "/GPIO15") (class "Default")
      (node (ref "J1") (pin "18") (pinfunction "18_18") (pintype "passive"))
      (node (ref "U1") (pin "19") (pinfunction "GPIO15/RTC_GPIO15/U0RTS/ADC2_CH4/XTAL_32K_P_19") (pintype "passive"))
    )
    (net (code "39") (name "/GPIO16") (class "Default")
      (node (ref "J1") (pin "19") (pinfunction "19_19") (pintype "passive"))
      (node (ref "U1") (pin "20") (pinfunction "GPIO16/RTC_GPIO16/U0CTS/ADC2_CH5/XTAL_32K_N_20") (pintype "passive"))
    )
    (net (code "40") (name "/GPIO17") (class "Default")
      (node (ref "J1") (pin "20") (pinfunction "20_20") (pintype "passive"))
      (node (ref "U1") (pin "21") (pinfunction "GPIO17/RTC_GPIO17/U1TXD/ADC2_CH6_21") (pintype "passive"))
    )
    (net (code "41") (name "/GPIO18") (class "Default")
      (node (ref "J1") (pin "21") (pinfunction "21_21") (pintype "passive"))
      (node (ref "U1") (pin "22") (pinfunction "GPIO18/RTC_GPIO18/U1RXD/ADC2_CH7/CLK_OUT3_22") (pintype "passive"))
    )
    (net (code "42") (name "/GPIO21") (class "Default")
      (node (ref "J2") (pin "19") (pinfunction "19_19") (pintype "passive"))
      (node (ref "U1") (pin "25") (pinfunction "GPIO21/RTC_GPIO21_25") (pintype "passive"))
    )
    (net (code "43") (name "/GPIO26") (class "Default")
      (node (ref "J2") (pin "18") (pinfunction "18_18") (pintype "passive"))
      (node (ref "U1") (pin "26") (pinfunction "GPIO26/SPICS1_26") (pintype "passive"))
    )
    (net (code "44") (name "/GPIO33") (class "Default")
      (node (ref "J2") (pin "17") (pinfunction "17_17") (pintype "passive"))
      (node (ref "U1") (pin "28") (pinfunction "GPIO33/SPIIO4/FSPIHD/SUBSPIHD_28") (pintype "passive"))
    )
    (net (code "45") (name "/GPIO34") (class "Default")
      (node (ref "J2") (pin "16") (pinfunction "16_16") (pintype "passive"))
      (node (ref "U1") (pin "29") (pinfunction "GPIO34/SPIIO5/FSPICS0/SUBSPICS0_29") (pintype "passive"))
    )
    (net (code "46") (name "/GPIO35") (class "Default")
      (node (ref "J2") (pin "15") (pinfunction "15_15") (pintype "passive"))
      (node (ref "U1") (pin "31") (pinfunction "GPIO35/SPIIO6/FSPID/SUBSPID_31") (pintype "passive"))
    )
    (net (code "47") (name "/GPIO36") (class "Default")
      (node (ref "J2") (pin "14") (pinfunction "14_14") (pintype "passive"))
      (node (ref "U1") (pin "32") (pinfunction "GPIO36/SPIIO7/FSPICLK/SUBSPICLK_32") (pintype "passive"))
    )
    (net (code "48") (name "/GPIO37") (class "Default")
      (node (ref "J2") (pin "13") (pinfunction "13_13") (pintype "passive"))
      (node (ref "U1") (pin "33") (pinfunction "GPIO37/SPIDQS/FSPIQ/SUBSPIQ_33") (pintype "passive"))
    )
    (net (code "49") (name "/GPIO38") (class "Default")
      (node (ref "J2") (pin "12") (pinfunction "12_12") (pintype "passive"))
      (node (ref "U1") (pin "34") (pinfunction "GPIO38/FSPIWP/SUBSPIWP_34") (pintype "passive"))
    )
    (net (code "50") (name "/GPIO39") (class "Default")
      (node (ref "J2") (pin "11") (pinfunction "11_11") (pintype "passive"))
      (node (ref "U1") (pin "35") (pinfunction "MTCK/GPIO39/CLK_OUT3/SUBSPICS1_35") (pintype "passive"))
    )
    (net (code "51") (name "/GPIO40") (class "Default")
      (node (ref "J2") (pin "10") (pinfunction "10_10") (pintype "passive"))
      (node (ref "U1") (pin "36") (pinfunction "MTDO/GPIO40/CLK_OUT2_36") (pintype "passive"))
    )
    (net (code "52") (name "/GPIO41") (class "Default")
      (node (ref "J2") (pin "9") (pinfunction "9_9") (pintype "passive"))
      (node (ref "U1") (pin "37") (pinfunction "MTDI/GPIO41/CLK_OUT1_37") (pintype "passive"))
    )
    (net (code "53") (name "/GPIO42") (class "Default")
      (node (ref "J2") (pin "8") (pinfunction "8_8") (pintype "passive"))
      (node (ref "U1") (pin "38") (pinfunction "MTMS/GPIO42_38") (pintype "passive"))
    )
    (net (code "54") (name "/GPIO45") (class "Default")
      (node (ref "J2") (pin "5") (pinfunction "5_5") (pintype "passive"))
      (node (ref "U1") (pin "41") (pinfunction "GPIO45_41") (pintype "passive"))
    )
    (net (code "55") (name "/GPIO46") (class "Default")
      (node (ref "J2") (pin "4") (pinfunction "4_4") (pintype "passive"))
      (node (ref "U1") (pin "44") (pinfunction "GPIO46_44") (pintype "passive"))
    )
    (net (code "56") (name "/GPIO47") (class "Default")
      (node (ref "J2") (pin "23") (pinfunction "23_23") (pintype "passive"))
      (node (ref "U1") (pin "27") (pinfunction "GPIO47/SPICLK_P_DIFF/SUBSPICLK_P_DIFF_27") (pintype "passive"))
    )
    (net (code "57") (name "/GPIO48") (class "Default")
      (node (ref "J2") (pin "22") (pinfunction "22_22") (pintype "passive"))
      (node (ref "U1") (pin "30") (pinfunction "GPIO48/SPICLK_N_DIFF/SUBSPICLK_N_DIFF_30") (pintype "passive"))
    )
    (net (code "58") (name "/RTS_FTDI") (class "Default")
      (node (ref "Q1") (pin "2") (pinfunction "E_2") (pintype "passive"))
      (node (ref "R18") (pin "1") (pinfunction "1_1") (pintype "passive"))
      (node (ref "U2") (pin "19") (pinfunction "~{RTS}_19") (pintype "passive"))
    )
    (net (code "59") (name "/RXD_FTDI") (class "Default")
      (node (ref "R19") (pin "2") (pinfunction "2_2") (pintype "passive"))
      (node (ref "U2") (pin "1") (pinfunction "RXD_1") (pintype "passive"))
    )
    (net (code "60") (name "/TXD_FTDI") (class "Default")
      (node (ref "R20") (pin "2") (pinfunction "2_2") (pintype "passive"))
      (node (ref "U2") (pin "17") (pinfunction "TXD_17") (pintype "passive"))
    )
    (net (code "61") (name "/U0RXD") (class "Default")
      (node (ref "J2") (pin "6") (pinfunction "6_6") (pintype "passive"))
      (node (ref "R20") (pin "1") (pinfunction "1_1") (pintype "passive"))
      (node (ref "U1") (pin "40") (pinfunction "U0RXD/GPIO44/CLK_OUT2_40") (pintype "passive"))
    )
    (net (code "62") (name "/U0TXD") (class "Default")
      (node (ref "J2") (pin "7") (pinfunction "7_7") (pintype "passive"))
      (node (ref "R19") (pin "1") (pinfunction "1_1") (pintype "passive"))
      (node (ref "U1") (pin "39") (pinfunction "U0TXD/GPIO43/CLK_OUT1_39") (pintype "passive"))
    )
    (net (code "63") (name "/VBUS_SENSE") (class "Default")
      (node (ref "R10") (pin "1") (pinfunction "1_1") (pintype "passive"))
      (node (ref "R13") (pin "2") (pinfunction "2_2") (pintype "passive"))
      (node (ref "U2") (pin "16") (pinfunction "CBUS3_16") (pintype "passive"))
    )
    (net (code "64") (name "GND") (class "Default")
      (node (ref "C1") (pin "1") (pinfunction "1_1") (pintype "passive"))
      (node (ref "C10") (pin "1") (pinfunction "1_1") (pintype "passive"))
      (node (ref "C11") (pin "1") (pinfunction "1_1") (pintype "passive"))
      (node (ref "C12") (pin "1") (pinfunction "1_1") (pintype "passive"))
      (node (ref "C13") (pin "1") (pinfunction "1_1") (pintype "passive"))
      (node (ref "C14") (pin "1") (pinfunction "1_1") (pintype "passive"))
      (node (ref "C15") (pin "1") (pinfunction "1_1") (pintype "passive"))
      (node (ref "C16") (pin "1") (pinfunction "1_1") (pintype "passive"))
      (node (ref "C17") (pin "1") (pinfunction "1_1") (pintype "passive"))
      (node (ref "C2") (pin "1") (pinfunction "1_1") (pintype "passive"))
      (node (ref "C3") (pin "1") (pinfunction "1_1") (pintype "passive"))
      (node (ref "C4") (pin "1") (pinfunction "1_1") (pintype "passive"))
      (node (ref "C5") (pin "1") (pinfunction "1_1") (pintype "passive"))
      (node (ref "C6") (pin "1") (pinfunction "1_1") (pintype "passive"))
      (node (ref "C7") (pin "1") (pinfunction "1_1") (pintype "passive"))
      (node (ref "C8") (pin "1") (pinfunction "1_1") (pintype "passive"))
      (node (ref "C9") (pin "1") (pinfunction "1_1") (pintype "passive"))
      (node (ref "D1") (pin "1") (pinfunction "1_1") (pintype "passive"))
      (node (ref "D2") (pin "1") (pinfunction "1_1") (pintype "passive"))
      (node (ref "D3") (pin "1") (pinfunction "1_1") (pintype "passive"))
      (node (ref "D4") (pin "1") (pinfunction "1_1") (pintype "passive"))
      (node (ref "D6") (pin "1") (pinfunction "1_1") (pintype "passive"))
      (node (ref "D7") (pin "1") (pinfunction "1_1") (pintype "passive"))
      (node (ref "D8") (pin "1") (pinfunction "1_1") (pintype "passive"))
      (node (ref "J1") (pin "1") (pinfunction "1_1") (pintype "passive"))
      (node (ref "J1") (pin "23") (pinfunction "23_23") (pintype "passive"))
      (node (ref "J2") (pin "2") (pinfunction "2_2") (pintype "passive"))
      (node (ref "J2") (pin "24") (pinfunction "24_24") (pintype "passive"))
      (node (ref "J3") (pin "A1B12") (pinfunction "GND_A1B12_A1B12") (pintype "passive"))
      (node (ref "J3") (pin "B1A12") (pinfunction "GND_B1A12_B1A12") (pintype "passive"))
      (node (ref "J3") (pin "S1") (pinfunction "SHIELD_1_S1") (pintype "passive"))
      (node (ref "J3") (pin "S2") (pinfunction "SHIELD_2_S2") (pintype "passive"))
      (node (ref "J3") (pin "S3") (pinfunction "SHIELD_3_S3") (pintype "passive"))
      (node (ref "J3") (pin "S4") (pinfunction "SHIELD_4_S4") (pintype "passive"))
      (node (ref "J4") (pin "A1B12") (pinfunction "GND_A1B12_A1B12") (pintype "passive"))
      (node (ref "J4") (pin "B1A12") (pinfunction "GND_B1A12_B1A12") (pintype "passive"))
      (node (ref "J4") (pin "S1") (pinfunction "SHIELD_1_S1") (pintype "passive"))
      (node (ref "J4") (pin "S2") (pinfunction "SHIELD_2_S2") (pintype "passive"))
      (node (ref "J4") (pin "S3") (pinfunction "SHIELD_3_S3") (pintype "passive"))
      (node (ref "J4") (pin "S4") (pinfunction "SHIELD_4_S4") (pintype "passive"))
      (node (ref "R11") (pin "1") (pinfunction "1_1") (pintype "passive"))
      (node (ref "R12") (pin "1") (pinfunction "1_1") (pintype "passive"))
      (node (ref "R13") (pin "1") (pinfunction "1_1") (pintype "passive"))
      (node (ref "R14") (pin "1") (pinfunction "1_1") (pintype "passive"))
      (node (ref "R15") (pin "1") (pinfunction "1_1") (pintype "passive"))
      (node (ref "R9") (pin "2") (pinfunction "2_2") (pintype "passive"))
      (node (ref "SW1") (pin "3") (pinfunction "3_3") (pintype "passive"))
      (node (ref "SW1") (pin "4") (pinfunction "4_4") (pintype "passive"))
      (node (ref "SW2") (pin "3") (pinfunction "3_3") (pintype "passive"))
      (node (ref "SW2") (pin "4") (pinfunction "4_4") (pintype "passive"))
      (node (ref "U1") (pin "1") (pinfunction "GND1_1") (pintype "passive"))
      (node (ref "U1") (pin "2") (pinfunction "GND2_2") (pintype "passive"))
      (node (ref "U1") (pin "42") (pinfunction "GND_42") (pintype "passive"))
      (node (ref "U1") (pin "43") (pinfunction "GND_43") (pintype "passive"))
      (node (ref "U1") (pin "46") (pinfunction "GND_46_46") (pintype "passive"))
      (node (ref "U1") (pin "47") (pinfunction "GND_47_47") (pintype "passive"))
      (node (ref "U1") (pin "48") (pinfunction "GND_48_48") (pintype "passive"))
      (node (ref "U1") (pin "49") (pinfunction "GND_49_49") (pintype "passive"))
      (node (ref "U1") (pin "50") (pinfunction "GND_50_50") (pintype "passive"))
      (node (ref "U1") (pin "51") (pinfunction "GND_51_51") (pintype "passive"))
      (node (ref "U1") (pin "52") (pinfunction "GND_52_52") (pintype "passive"))
      (node (ref "U1") (pin "53") (pinfunction "GND_53_53") (pintype "passive"))
      (node (ref "U1") (pin "54") (pinfunction "GND_54_54") (pintype "passive"))
      (node (ref "U1") (pin "55") (pinfunction "GND_55_55") (pintype "passive"))
      (node (ref "U1") (pin "56") (pinfunction "GND_56_56") (pintype "passive"))
      (node (ref "U1") (pin "57") (pinfunction "GND_57_57") (pintype "passive"))
      (node (ref "U1") (pin "58") (pinfunction "GND_58_58") (pintype "passive"))
      (node (ref "U1") (pin "59") (pinfunction "GND_59_59") (pintype "passive"))
      (node (ref "U1") (pin "60") (pinfunction "GND_60_60") (pintype "passive"))
      (node (ref "U1") (pin "61") (pinfunction "GND_61_61") (pintype "passive"))
      (node (ref "U1") (pin "62") (pinfunction "GND_62_62") (pintype "passive"))
      (node (ref "U1") (pin "63") (pinfunction "GND_63_63") (pintype "passive"))
      (node (ref "U1") (pin "64") (pinfunction "GND_64_64") (pintype "passive"))
      (node (ref "U1") (pin "65") (pinfunction "GND_65_65") (pintype "passive"))
      (node (ref "U1") (pin "66") (pinfunction "GND_66_66") (pintype "passive"))
      (node (ref "U1") (pin "67") (pinfunction "GND_67_67") (pintype "passive"))
      (node (ref "U1") (pin "68") (pinfunction "GND_68_68") (pintype "passive"))
      (node (ref "U1") (pin "69") (pinfunction "GND_69_69") (pintype "passive"))
      (node (ref "U1") (pin "70") (pinfunction "GND_70_70") (pintype "passive"))
      (node (ref "U1") (pin "71") (pinfunction "GND_71_71") (pintype "passive"))
      (node (ref "U1") (pin "72") (pinfunction "GND_72_72") (pintype "passive"))
      (node (ref "U1") (pin "73") (pinfunction "GND_73_73") (pintype "passive"))
      (node (ref "U2") (pin "13") (pinfunction "GND_13") (pintype "passive"))
      (node (ref "U2") (pin "21") (pinfunction "GND_21") (pintype "passive"))
      (node (ref "U2") (pin "3") (pinfunction "GND_3") (pintype "passive"))
      (node (ref "U3") (pin "2") (pinfunction "GND_2") (pintype "power_in"))
      (node (ref "U3") (pin "4") (pinfunction "GND_4") (pintype "power_in"))
    )
    (net (code "65") (name "Net-(D1-Pad2)") (class "Default")
      (node (ref "D1") (pin "2") (pinfunction "2_2") (pintype "passive"))
      (node (ref "R3") (pin "1") (pinfunction "1_1") (pintype "passive"))
    )
    (net (code "66") (name "Net-(D5-Pad2)") (class "Default")
      (node (ref "D5") (pin "2") (pinfunction "2_2") (pintype "passive"))
      (node (ref "R8") (pin "1") (pinfunction "1_1") (pintype "passive"))
    )
    (net (code "67") (name "Net-(J3-CC1)") (class "Default")
      (node (ref "J3") (pin "A5") (pinfunction "CC1_A5") (pintype "passive"))
      (node (ref "R12") (pin "2") (pinfunction "2_2") (pintype "passive"))
    )
    (net (code "68") (name "Net-(J3-CC2)") (class "Default")
      (node (ref "J3") (pin "B5") (pinfunction "CC2_B5") (pintype "passive"))
      (node (ref "R11") (pin "2") (pinfunction "2_2") (pintype "passive"))
    )
    (net (code "69") (name "Net-(J4-CC1)") (class "Default")
      (node (ref "J4") (pin "A5") (pinfunction "CC1_A5") (pintype "passive"))
      (node (ref "R15") (pin "2") (pinfunction "2_2") (pintype "passive"))
    )
    (net (code "70") (name "Net-(J4-CC2)") (class "Default")
      (node (ref "J4") (pin "B5") (pinfunction "CC2_B5") (pintype "passive"))
      (node (ref "R14") (pin "2") (pinfunction "2_2") (pintype "passive"))
    )
    (net (code "71") (name "Net-(Q1-B)") (class "Default")
      (node (ref "Q1") (pin "1") (pinfunction "B_1") (pintype "passive"))
      (node (ref "R16") (pin "2") (pinfunction "2_2") (pintype "passive"))
    )
    (net (code "72") (name "Net-(Q2-B)") (class "Default")
      (node (ref "Q2") (pin "1") (pinfunction "B_1") (pintype "passive"))
      (node (ref "R18") (pin "2") (pinfunction "2_2") (pintype "passive"))
    )
    (net (code "73") (name "Net-(U2-CBUS0)") (class "Default")
      (node (ref "R9") (pin "1") (pinfunction "1_1") (pintype "passive"))
      (node (ref "U2") (pin "15") (pinfunction "CBUS0_15") (pintype "passive"))
    )
    (net (code "74") (name "Net-(U2-~{RESET})") (class "Default")
      (node (ref "C8") (pin "2") (pinfunction "2_2") (pintype "passive"))
      (node (ref "R7") (pin "2") (pinfunction "2_2") (pintype "passive"))
      (node (ref "U2") (pin "11") (pinfunction "~{RESET}_11") (pintype "passive"))
    )
    (net (code "75") (name "unconnected-(J1-Pad24)") (class "Default")
      (node (ref "J1") (pin "24") (pinfunction "24_24") (pintype "passive"))
    )
    (net (code "76") (name "unconnected-(J3-SBU1-PadA8)") (class "Default")
      (node (ref "J3") (pin "A8") (pinfunction "SBU1_A8") (pintype "passive+no_connect"))
    )
    (net (code "77") (name "unconnected-(J3-SBU2-PadB8)") (class "Default")
      (node (ref "J3") (pin "B8") (pinfunction "SBU2_B8") (pintype "passive+no_connect"))
    )
    (net (code "78") (name "unconnected-(J4-SBU1-PadA8)") (class "Default")
      (node (ref "J4") (pin "A8") (pinfunction "SBU1_A8") (pintype "passive+no_connect"))
    )
    (net (code "79") (name "unconnected-(J4-SBU2-PadB8)") (class "Default")
      (node (ref "J4") (pin "B8") (pinfunction "SBU2_B8") (pintype "passive+no_connect"))
    )
    (net (code "80") (name "unconnected-(U2-CBUS1-Pad14)") (class "Default")
      (node (ref "U2") (pin "14") (pinfunction "CBUS1_14") (pintype "passive+no_connect"))
    )
    (net (code "81") (name "unconnected-(U2-CBUS2-Pad7)") (class "Default")
      (node (ref "U2") (pin "7") (pinfunction "CBUS2_7") (pintype "passive+no_connect"))
    )
    (net (code "82") (name "unconnected-(U2-~{CTS}-Pad6)") (class "Default")
      (node (ref "U2") (pin "6") (pinfunction "~{CTS}_6") (pintype "passive+no_connect"))
    )
    (net (code "83") (name "unconnected-(U2-~{DCD}-Pad5)") (class "Default")
      (node (ref "U2") (pin "5") (pinfunction "~{DCD}_5") (pintype "passive+no_connect"))
    )
    (net (code "84") (name "unconnected-(U2-~{DSR}-Pad4)") (class "Default")
      (node (ref "U2") (pin "4") (pinfunction "~{DSR}_4") (pintype "passive+no_connect"))
    )
    (net (code "85") (name "unconnected-(U2-~{RI}-Pad2)") (class "Default")
      (node (ref "U2") (pin "2") (pinfunction "~{RI}_2") (pintype "passive+no_connect"))
    )
  )
)
